# rgb-bar-graph-daughterboard.net
KiCad netlist of a schematic drawn in EAGLE
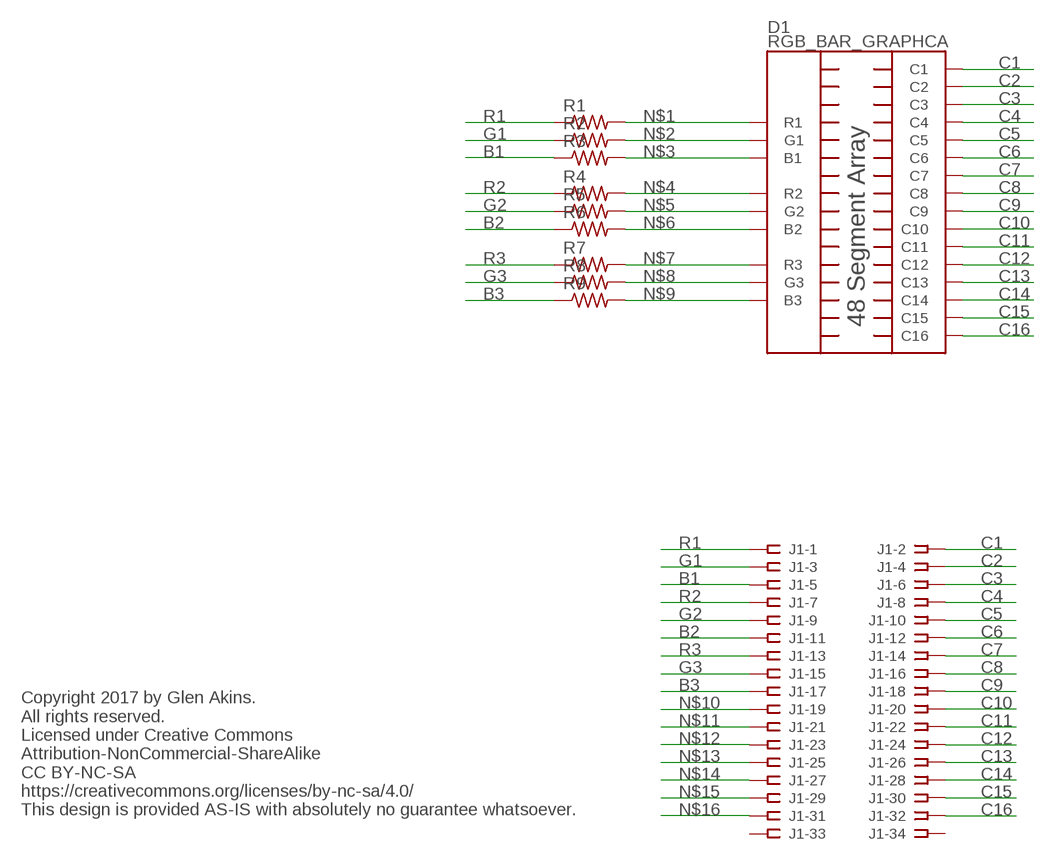
[diagram p0: schematic, sheet 1]

(export (version "E")
  (design (tool "Eeschema 10.0.6"))
  (components
    (comp (ref "D1")
      (value "RGB_BAR_GRAPHCA")
      (footprint "eagle-import:RGB_BAR_GRAPH")
      (libsource (lib "eagle-import") (part "RGB_BAR_GRAPHCA"))
    )
    (comp (ref "J1")
      (value "RGB-BAR-GRAPH-2X17-MOD-PADS")
      (footprint "eagle-import:RGB-BAR-GRAPH-SMD-34-PIN")
      (libsource (lib "eagle-import") (part "RGB-BAR-GRAPH-2X17-MOD-PADS"))
    )
    (comp (ref "R1")
      (value "R-US_R1206")
      (footprint "eagle-import:R1206")
      (libsource (lib "eagle-import") (part "R-US_R1206"))
    )
    (comp (ref "R2")
      (value "R-US_R1206")
      (footprint "eagle-import:R1206")
      (libsource (lib "eagle-import") (part "R-US_R1206"))
    )
    (comp (ref "R3")
      (value "R-US_R1206")
      (footprint "eagle-import:R1206")
      (libsource (lib "eagle-import") (part "R-US_R1206"))
    )
    (comp (ref "R4")
      (value "R-US_R1206")
      (footprint "eagle-import:R1206")
      (libsource (lib "eagle-import") (part "R-US_R1206"))
    )
    (comp (ref "R5")
      (value "R-US_R1206")
      (footprint "eagle-import:R1206")
      (libsource (lib "eagle-import") (part "R-US_R1206"))
    )
    (comp (ref "R6")
      (value "R-US_R1206")
      (footprint "eagle-import:R1206")
      (libsource (lib "eagle-import") (part "R-US_R1206"))
    )
    (comp (ref "R7")
      (value "R-US_R1206")
      (footprint "eagle-import:R1206")
      (libsource (lib "eagle-import") (part "R-US_R1206"))
    )
    (comp (ref "R8")
      (value "R-US_R1206")
      (footprint "eagle-import:R1206")
      (libsource (lib "eagle-import") (part "R-US_R1206"))
    )
    (comp (ref "R9")
      (value "R-US_R1206")
      (footprint "eagle-import:R1206")
      (libsource (lib "eagle-import") (part "R-US_R1206"))
    )
  )
  (nets
    (net (code "1") (name "/B1") (class "Default")
      (node (ref "J1") (pin "5") (pinfunction "1_5") (pintype "passive"))
      (node (ref "R3") (pin "1") (pinfunction "1_1") (pintype "passive"))
    )
    (net (code "2") (name "/B2") (class "Default")
      (node (ref "J1") (pin "11") (pinfunction "1_11") (pintype "passive"))
      (node (ref "R6") (pin "1") (pinfunction "1_1") (pintype "passive"))
    )
    (net (code "3") (name "/B3") (class "Default")
      (node (ref "J1") (pin "17") (pinfunction "1_17") (pintype "passive"))
      (node (ref "R9") (pin "1") (pinfunction "1_1") (pintype "passive"))
    )
    (net (code "4") (name "/C1") (class "Default")
      (node (ref "D1") (pin "1") (pinfunction "C1_1") (pintype "bidirectional"))
      (node (ref "J1") (pin "2") (pinfunction "1_2") (pintype "passive"))
    )
    (net (code "5") (name "/C2") (class "Default")
      (node (ref "D1") (pin "25") (pinfunction "C2_25") (pintype "bidirectional"))
      (node (ref "J1") (pin "4") (pinfunction "1_4") (pintype "passive"))
    )
    (net (code "6") (name "/C3") (class "Default")
      (node (ref "D1") (pin "3") (pinfunction "C3_3") (pintype "bidirectional"))
      (node (ref "J1") (pin "6") (pinfunction "1_6") (pintype "passive"))
    )
    (net (code "7") (name "/C4") (class "Default")
      (node (ref "D1") (pin "4") (pinfunction "C4_4") (pintype "bidirectional"))
      (node (ref "J1") (pin "8") (pinfunction "1_8") (pintype "passive"))
    )
    (net (code "8") (name "/C5") (class "Default")
      (node (ref "D1") (pin "23") (pinfunction "C5_23") (pintype "bidirectional"))
      (node (ref "J1") (pin "10") (pinfunction "1_10") (pintype "passive"))
    )
    (net (code "9") (name "/C6") (class "Default")
      (node (ref "D1") (pin "5") (pinfunction "C6_5") (pintype "bidirectional"))
      (node (ref "J1") (pin "12") (pinfunction "1_12") (pintype "passive"))
    )
    (net (code "10") (name "/C7") (class "Default")
      (node (ref "D1") (pin "22") (pinfunction "C7_22") (pintype "bidirectional"))
      (node (ref "J1") (pin "14") (pinfunction "1_14") (pintype "passive"))
    )
    (net (code "11") (name "/C8") (class "Default")
      (node (ref "D1") (pin "21") (pinfunction "C8_21") (pintype "bidirectional"))
      (node (ref "J1") (pin "16") (pinfunction "1_16") (pintype "passive"))
    )
    (net (code "12") (name "/C9") (class "Default")
      (node (ref "D1") (pin "20") (pinfunction "C9_20") (pintype "bidirectional"))
      (node (ref "J1") (pin "18") (pinfunction "1_18") (pintype "passive"))
    )
    (net (code "13") (name "/C10") (class "Default")
      (node (ref "D1") (pin "8") (pinfunction "C10_8") (pintype "bidirectional"))
      (node (ref "J1") (pin "20") (pinfunction "1_20") (pintype "passive"))
    )
    (net (code "14") (name "/C11") (class "Default")
      (node (ref "D1") (pin "19") (pinfunction "C11_19") (pintype "bidirectional"))
      (node (ref "J1") (pin "22") (pinfunction "1_22") (pintype "passive"))
    )
    (net (code "15") (name "/C12") (class "Default")
      (node (ref "D1") (pin "18") (pinfunction "C12_18") (pintype "bidirectional"))
      (node (ref "J1") (pin "24") (pinfunction "1_24") (pintype "passive"))
    )
    (net (code "16") (name "/C13") (class "Default")
      (node (ref "D1") (pin "10") (pinfunction "C13_10") (pintype "bidirectional"))
      (node (ref "J1") (pin "26") (pinfunction "1_26") (pintype "passive"))
    )
    (net (code "17") (name "/C14") (class "Default")
      (node (ref "D1") (pin "11") (pinfunction "C14_11") (pintype "bidirectional"))
      (node (ref "J1") (pin "28") (pinfunction "1_28") (pintype "passive"))
    )
    (net (code "18") (name "/C15") (class "Default")
      (node (ref "D1") (pin "15") (pinfunction "C15_15") (pintype "bidirectional"))
      (node (ref "J1") (pin "30") (pinfunction "1_30") (pintype "passive"))
    )
    (net (code "19") (name "/C16") (class "Default")
      (node (ref "D1") (pin "12") (pinfunction "C16_12") (pintype "bidirectional"))
      (node (ref "J1") (pin "32") (pinfunction "1_32") (pintype "passive"))
    )
    (net (code "20") (name "/G1") (class "Default")
      (node (ref "J1") (pin "3") (pinfunction "1_3") (pintype "passive"))
      (node (ref "R2") (pin "1") (pinfunction "1_1") (pintype "passive"))
    )
    (net (code "21") (name "/G2") (class "Default")
      (node (ref "J1") (pin "9") (pinfunction "1_9") (pintype "passive"))
      (node (ref "R5") (pin "1") (pinfunction "1_1") (pintype "passive"))
    )
    (net (code "22") (name "/G3") (class "Default")
      (node (ref "J1") (pin "15") (pinfunction "1_15") (pintype "passive"))
      (node (ref "R8") (pin "1") (pinfunction "1_1") (pintype "passive"))
    )
    (net (code "23") (name "/N$1") (class "Default")
      (node (ref "D1") (pin "9") (pinfunction "R1_9") (pintype "bidirectional"))
      (node (ref "R1") (pin "2") (pinfunction "2_2") (pintype "passive"))
    )
    (net (code "24") (name "/N$2") (class "Default")
      (node (ref "D1") (pin "7") (pinfunction "G1_7") (pintype "bidirectional"))
      (node (ref "R2") (pin "2") (pinfunction "2_2") (pintype "passive"))
    )
    (net (code "25") (name "/N$3") (class "Default")
      (node (ref "D1") (pin "24") (pinfunction "B1_24") (pintype "bidirectional"))
      (node (ref "R3") (pin "2") (pinfunction "2_2") (pintype "passive"))
    )
    (net (code "26") (name "/N$4") (class "Default")
      (node (ref "D1") (pin "17") (pinfunction "R2_17") (pintype "bidirectional"))
      (node (ref "R4") (pin "2") (pinfunction "2_2") (pintype "passive"))
    )
    (net (code "27") (name "/N$5") (class "Default")
      (node (ref "D1") (pin "16") (pinfunction "G2_16") (pintype "bidirectional"))
      (node (ref "R5") (pin "2") (pinfunction "2_2") (pintype "passive"))
    )
    (net (code "28") (name "/N$6") (class "Default")
      (node (ref "D1") (pin "6") (pinfunction "B2_6") (pintype "bidirectional"))
      (node (ref "R6") (pin "2") (pinfunction "2_2") (pintype "passive"))
    )
    (net (code "29") (name "/N$7") (class "Default")
      (node (ref "D1") (pin "13") (pinfunction "R3_13") (pintype "bidirectional"))
      (node (ref "R7") (pin "2") (pinfunction "2_2") (pintype "passive"))
    )
    (net (code "30") (name "/N$8") (class "Default")
      (node (ref "D1") (pin "2") (pinfunction "G3_2") (pintype "bidirectional"))
      (node (ref "R8") (pin "2") (pinfunction "2_2") (pintype "passive"))
    )
    (net (code "31") (name "/N$9") (class "Default")
      (node (ref "D1") (pin "14") (pinfunction "B3_14") (pintype "bidirectional"))
      (node (ref "R9") (pin "2") (pinfunction "2_2") (pintype "passive"))
    )
    (net (code "32") (name "/N$10") (class "Default")
      (node (ref "J1") (pin "19") (pinfunction "1_19") (pintype "passive"))
    )
    (net (code "33") (name "/N$11") (class "Default")
      (node (ref "J1") (pin "21") (pinfunction "1_21") (pintype "passive"))
    )
    (net (code "34") (name "/N$12") (class "Default")
      (node (ref "J1") (pin "23") (pinfunction "1_23") (pintype "passive"))
    )
    (net (code "35") (name "/N$13") (class "Default")
      (node (ref "J1") (pin "25") (pinfunction "1_25") (pintype "passive"))
    )
    (net (code "36") (name "/N$14") (class "Default")
      (node (ref "J1") (pin "27") (pinfunction "1_27") (pintype "passive"))
    )
    (net (code "37") (name "/N$15") (class "Default")
      (node (ref "J1") (pin "29") (pinfunction "1_29") (pintype "passive"))
    )
    (net (code "38") (name "/N$16") (class "Default")
      (node (ref "J1") (pin "31") (pinfunction "1_31") (pintype "passive"))
    )
    (net (code "39") (name "/R1") (class "Default")
      (node (ref "J1") (pin "1") (pinfunction "1_1") (pintype "passive"))
      (node (ref "R1") (pin "1") (pinfunction "1_1") (pintype "passive"))
    )
    (net (code "40") (name "/R2") (class "Default")
      (node (ref "J1") (pin "7") (pinfunction "1_7") (pintype "passive"))
      (node (ref "R4") (pin "1") (pinfunction "1_1") (pintype "passive"))
    )
    (net (code "41") (name "/R3") (class "Default")
      (node (ref "J1") (pin "13") (pinfunction "1_13") (pintype "passive"))
      (node (ref "R7") (pin "1") (pinfunction "1_1") (pintype "passive"))
    )
    (net (code "42") (name "unconnected-(J1AA-1-Pad33)") (class "Default")
      (node (ref "J1") (pin "33") (pinfunction "1_33") (pintype "passive"))
    )
    (net (code "43") (name "unconnected-(J1AB-1-Pad34)") (class "Default")
      (node (ref "J1") (pin "34") (pinfunction "1_34") (pintype "passive"))
    )
  )
)
